# LED.net
KiCad netlist of a schematic drawn in Altium Designer
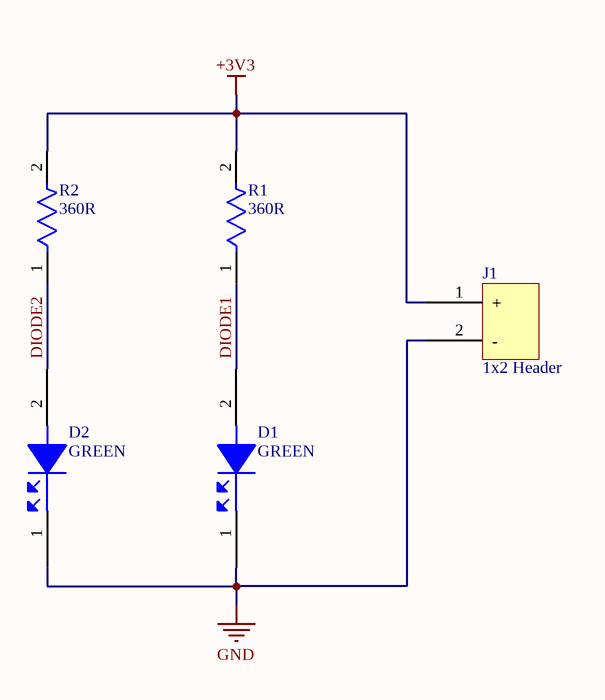
[diagram p0: LED.SchDoc]

(export (version "E")
  (design (tool "Eeschema 10.0.6"))
  (components
    (comp (ref "D1")
      (value "GREEN")
      (footprint "LED0603G")
      (description "LED SM 0603 3V -/1000/-MCD GREEN")
      (fields
        (field (name "MANUFACTURER") "Visual Communications")
        (field (name "MANUFACTURER PART NUMBER") "LSM0603453V")
      )
      (libsource (lib "LED_Schlib1") (part "LSM0603453V"))
    )
    (comp (ref "D2")
      (value "GREEN")
      (footprint "LED0603G")
      (description "LED SM 0603 3V -/1000/-MCD GREEN")
      (fields
        (field (name "MANUFACTURER") "Visual Communications")
        (field (name "MANUFACTURER PART NUMBER") "LSM0603453V")
      )
      (libsource (lib "LED_Schlib1") (part "LSM0603453V"))
    )
    (comp (ref "J1")
      (value "1x2 Header")
      (footprint "HDR1x2")
      (description "CONN HEADER VERT 2POS 2.54MM")
      (fields (field (name "MANUFACTURER") "Molex") (field (name "MANUFACTURER PART NUMBER") "22-27-2021"))
      (libsource (lib "LED_Schlib1") (part "22-27-2021"))
    )
    (comp (ref "R1")
      (value "360R")
      (footprint "R0805")
      (description "RES SMD 360 OHM 1% 1/8W 0805")
      (fields (field (name "TOLERANCE") "0.01") (field (name "MANUFACTURER") "Yageo"))
      (libsource (lib "LED_Schlib1") (part "1029c3af85768c4190bb7ad29bc67b5"))
    )
    (comp (ref "R2")
      (value "360R")
      (footprint "R0805")
      (description "RES SMD 360 OHM 1% 1/8W 0805")
      (fields (field (name "TOLERANCE") "0.01") (field (name "MANUFACTURER") "Yageo"))
      (libsource (lib "LED_Schlib1") (part "1029c3af85768c4190bb7ad29bc67b5"))
    )
  )
  (nets
    (net (code "1") (name "+3V3") (class "Default")
      (node (ref "J1") (pin "1") (pinfunction "+_1") (pintype "passive"))
      (node (ref "R1") (pin "2") (pinfunction "2_2") (pintype "passive"))
      (node (ref "R2") (pin "2") (pinfunction "2_2") (pintype "passive"))
    )
    (net (code "2") (name "/DIODE1") (class "Default")
      (node (ref "D1") (pin "2") (pinfunction "2_2") (pintype "passive"))
      (node (ref "R1") (pin "1") (pinfunction "1_1") (pintype "passive"))
    )
    (net (code "3") (name "/DIODE2") (class "Default")
      (node (ref "D2") (pin "2") (pinfunction "2_2") (pintype "passive"))
      (node (ref "R2") (pin "1") (pinfunction "1_1") (pintype "passive"))
    )
    (net (code "4") (name "GND") (class "Default")
      (node (ref "D1") (pin "1") (pinfunction "1_1") (pintype "passive"))
      (node (ref "D2") (pin "1") (pinfunction "1_1") (pintype "passive"))
      (node (ref "J1") (pin "2") (pinfunction "-_2") (pintype "passive"))
    )
  )
)
